# M401M.net
KiCad netlist of a schematic drawn in EAGLE
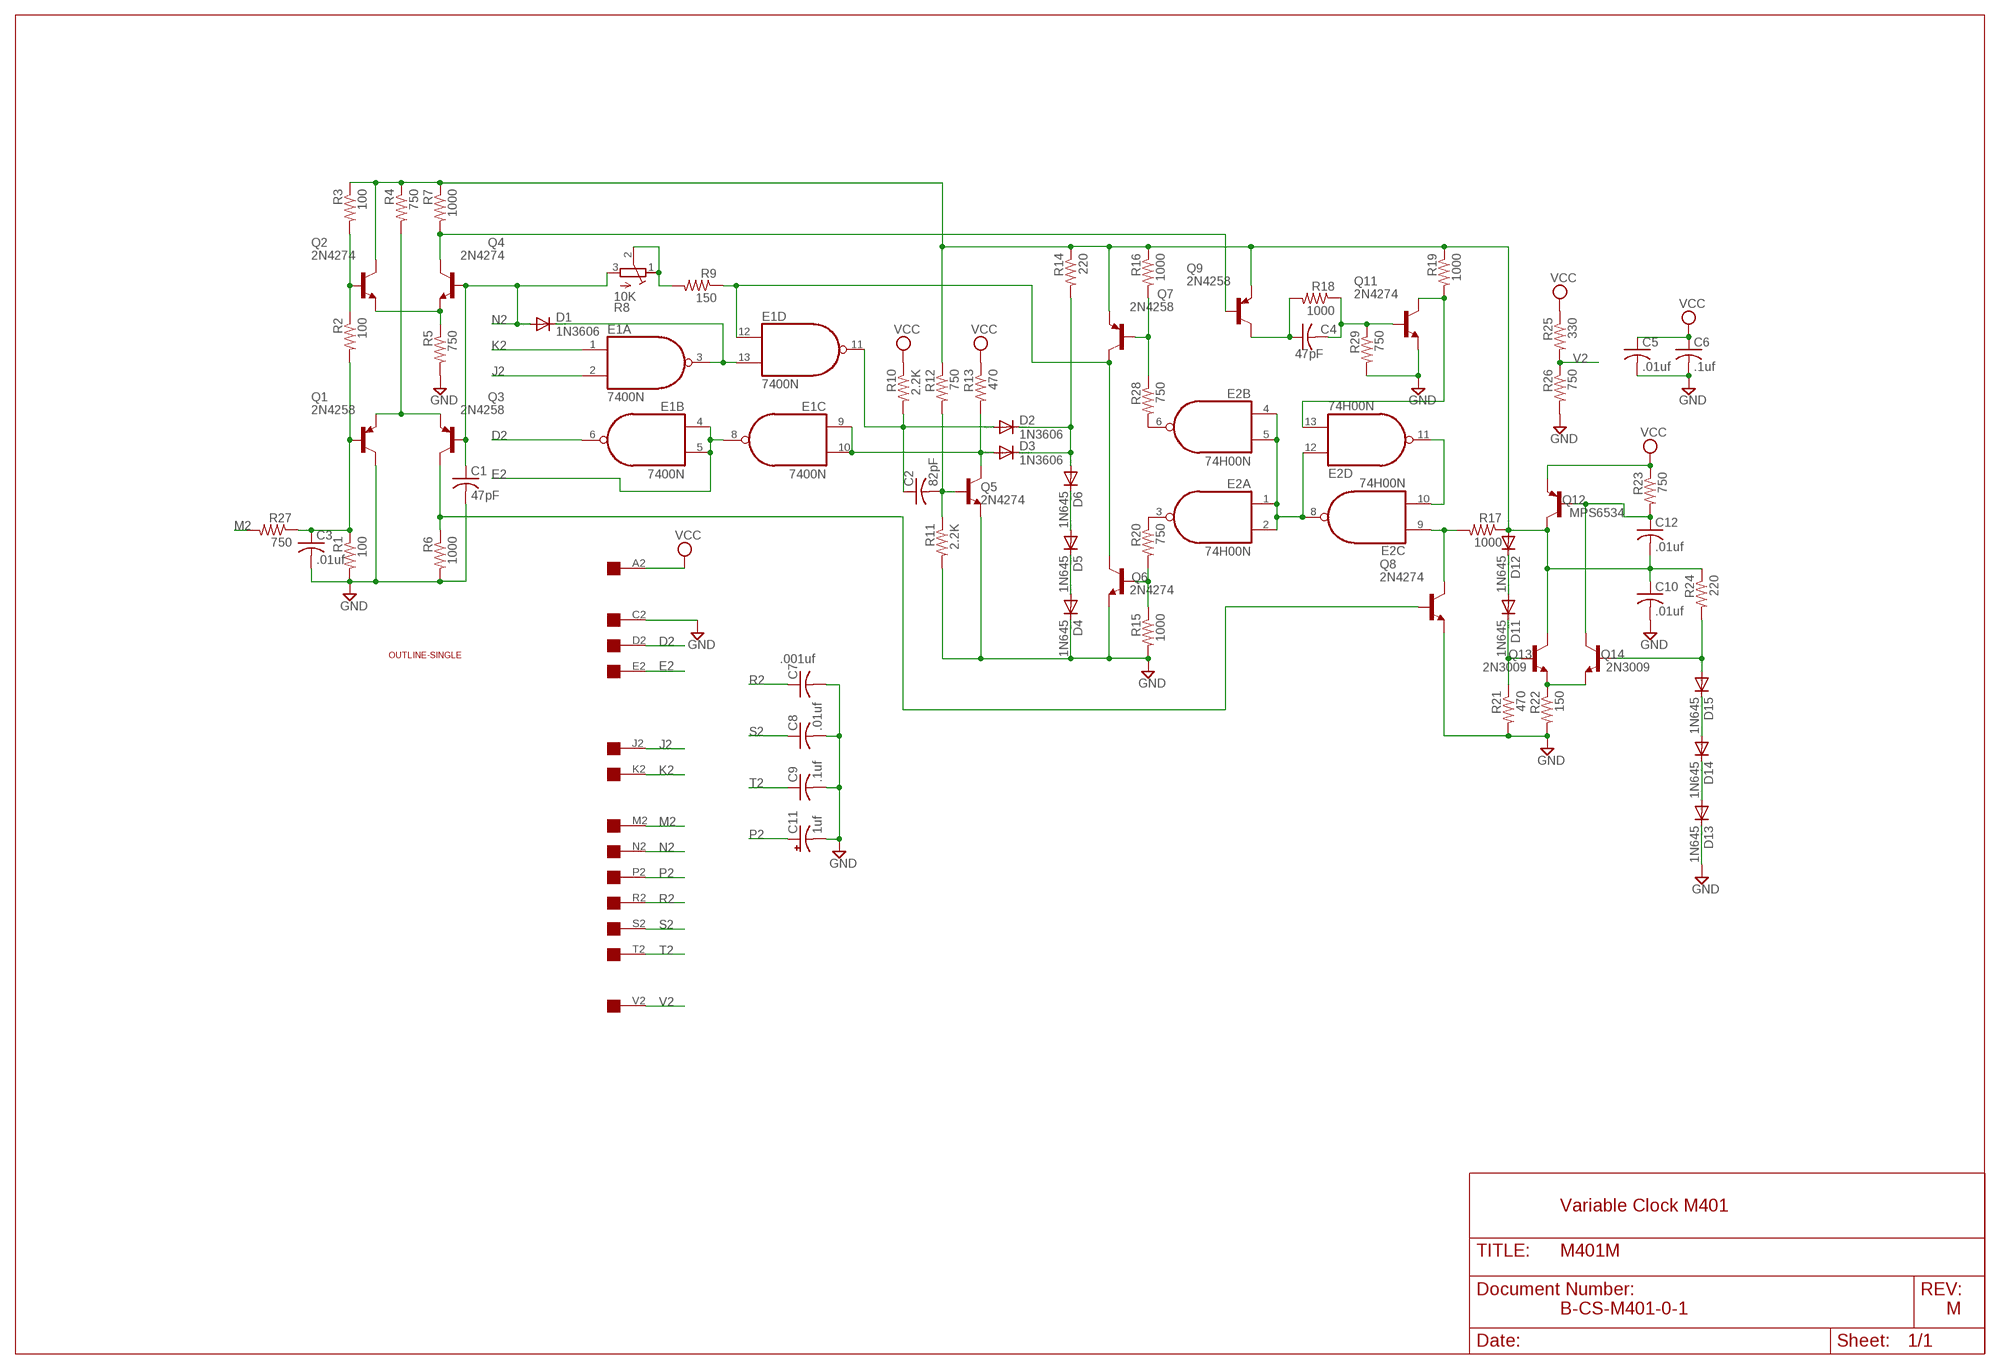
[diagram p0: schematic, sheet 1]

(export (version "E")
  (design (tool "Eeschema 10.0.6"))
  (components
    (comp (ref "C1")
      (value "47pF")
      (footprint "eagle-import:C050-025X075")
      (libsource (lib "eagle-import") (part "C-US050-025X075"))
    )
    (comp (ref "C2")
      (value "82pF")
      (footprint "eagle-import:C050-025X075")
      (libsource (lib "eagle-import") (part "C-US050-025X075"))
    )
    (comp (ref "C3")
      (value ".01uf")
      (footprint "eagle-import:C050-025X075")
      (libsource (lib "eagle-import") (part "C-US050-025X075"))
    )
    (comp (ref "C4")
      (value "47pF")
      (footprint "eagle-import:C050-025X075")
      (libsource (lib "eagle-import") (part "C-US050-025X075"))
    )
    (comp (ref "C5")
      (value ".01uf")
      (footprint "eagle-import:C050-025X075")
      (libsource (lib "eagle-import") (part "C-US050-025X075"))
    )
    (comp (ref "C6")
      (value ".1uf")
      (footprint "eagle-import:C102-043X133")
      (libsource (lib "eagle-import") (part "C-US102-043X133"))
    )
    (comp (ref "C7")
      (value ".001uf")
      (footprint "eagle-import:C050-025X075")
      (libsource (lib "eagle-import") (part "C-US050-025X075"))
    )
    (comp (ref "C8")
      (value ".01uf")
      (footprint "eagle-import:C225-062X268")
      (libsource (lib "eagle-import") (part "C-US225-062X268"))
    )
    (comp (ref "C9")
      (value ".1uf")
      (footprint "eagle-import:C275-093X316")
      (libsource (lib "eagle-import") (part "C-US275-093X316"))
    )
    (comp (ref "C10")
      (value ".01uf")
      (footprint "eagle-import:C050-025X075")
      (libsource (lib "eagle-import") (part "C-US050-025X075"))
    )
    (comp (ref "C11")
      (value "1uf")
      (footprint "eagle-import:E15-5")
      (libsource (lib "eagle-import") (part "CPOL-USE15-5AXIAL"))
    )
    (comp (ref "C12")
      (value ".01uf")
      (footprint "eagle-import:C050-025X075")
      (libsource (lib "eagle-import") (part "C-US050-025X075"))
    )
    (comp (ref "D1")
      (value "1N3606")
      (footprint "eagle-import:DO35-10")
      (libsource (lib "eagle-import") (part "1N4148DO35-10"))
    )
    (comp (ref "D2")
      (value "1N3606")
      (footprint "eagle-import:DO35-10")
      (libsource (lib "eagle-import") (part "1N4148DO35-10"))
    )
    (comp (ref "D3")
      (value "1N3606")
      (footprint "eagle-import:DO35-10")
      (libsource (lib "eagle-import") (part "1N4148DO35-10"))
    )
    (comp (ref "D4")
      (value "1N645")
      (footprint "eagle-import:DO35-10")
      (libsource (lib "eagle-import") (part "1N4148DO35-10"))
    )
    (comp (ref "D5")
      (value "1N645")
      (footprint "eagle-import:DO35-10")
      (libsource (lib "eagle-import") (part "1N4148DO35-10"))
    )
    (comp (ref "D6")
      (value "1N645")
      (footprint "eagle-import:DO35-10")
      (libsource (lib "eagle-import") (part "1N4148DO35-10"))
    )
    (comp (ref "D11")
      (value "1N645")
      (footprint "eagle-import:DO35-10")
      (libsource (lib "eagle-import") (part "1N4148DO35-10"))
    )
    (comp (ref "D12")
      (value "1N645")
      (footprint "eagle-import:DO35-10")
      (libsource (lib "eagle-import") (part "1N4148DO35-10"))
    )
    (comp (ref "D13")
      (value "1N645")
      (footprint "eagle-import:DO35-10")
      (libsource (lib "eagle-import") (part "1N4148DO35-10"))
    )
    (comp (ref "D14")
      (value "1N645")
      (footprint "eagle-import:DO35-10")
      (libsource (lib "eagle-import") (part "1N4148DO35-10"))
    )
    (comp (ref "D15")
      (value "1N645")
      (footprint "eagle-import:DO35-10")
      (libsource (lib "eagle-import") (part "1N4148DO35-10"))
    )
    (comp (ref "E1")
      (value "7400N")
      (footprint "eagle-import:DIL14")
      (libsource (lib "eagle-import") (part "7400N"))
    )
    (comp (ref "E2")
      (value "74H00N")
      (footprint "eagle-import:DIL14")
      (libsource (lib "eagle-import") (part "7400N"))
    )
    (comp (ref "Q1")
      (value "2N4258")
      (footprint "eagle-import:TO39")
      (libsource (lib "eagle-import") (part "-PNP-TO39-EBC2N3637"))
    )
    (comp (ref "Q2")
      (value "2N4274")
      (footprint "eagle-import:TO39")
      (libsource (lib "eagle-import") (part "-NPN-TO39-EBC2N3019"))
    )
    (comp (ref "Q3")
      (value "2N4258")
      (footprint "eagle-import:TO39")
      (libsource (lib "eagle-import") (part "-PNP-TO39-EBC2N3637"))
    )
    (comp (ref "Q4")
      (value "2N4274")
      (footprint "eagle-import:TO39")
      (libsource (lib "eagle-import") (part "-NPN-TO39-EBC2N3019"))
    )
    (comp (ref "Q5")
      (value "2N4274")
      (footprint "eagle-import:TO39")
      (libsource (lib "eagle-import") (part "-NPN-TO39-EBC2N3019"))
    )
    (comp (ref "Q6")
      (value "2N4274")
      (footprint "eagle-import:TO39")
      (libsource (lib "eagle-import") (part "-NPN-TO39-EBC2N3019"))
    )
    (comp (ref "Q7")
      (value "2N4258")
      (footprint "eagle-import:TO39")
      (libsource (lib "eagle-import") (part "-PNP-TO39-EBC2N3637"))
    )
    (comp (ref "Q8")
      (value "2N4274")
      (footprint "eagle-import:TO39")
      (libsource (lib "eagle-import") (part "-NPN-TO39-EBC2N3019"))
    )
    (comp (ref "Q9")
      (value "2N4258")
      (footprint "eagle-import:TO39")
      (libsource (lib "eagle-import") (part "-PNP-TO39-EBC2N3637"))
    )
    (comp (ref "Q11")
      (value "2N4274")
      (footprint "eagle-import:TO39")
      (libsource (lib "eagle-import") (part "-NPN-TO39-EBC2N3019"))
    )
    (comp (ref "Q12")
      (value "MPS6534")
      (footprint "eagle-import:TO39")
      (libsource (lib "eagle-import") (part "-PNP-TO39-EBC2N3637"))
    )
    (comp (ref "Q13")
      (value "2N3009")
      (footprint "eagle-import:TO39")
      (libsource (lib "eagle-import") (part "-NPN-TO39-EBC2N3019"))
    )
    (comp (ref "Q14")
      (value "2N3009")
      (footprint "eagle-import:TO39")
      (libsource (lib "eagle-import") (part "-NPN-TO39-EBC2N3019"))
    )
    (comp (ref "R1")
      (value "100")
      (footprint "eagle-import:0207_10")
      (libsource (lib "eagle-import") (part "R-US_0207/10"))
    )
    (comp (ref "R2")
      (value "100")
      (footprint "eagle-import:0207_10")
      (libsource (lib "eagle-import") (part "R-US_0207/10"))
    )
    (comp (ref "R3")
      (value "100")
      (footprint "eagle-import:0207_10")
      (libsource (lib "eagle-import") (part "R-US_0207/10"))
    )
    (comp (ref "R4")
      (value "750")
      (footprint "eagle-import:0207_10")
      (libsource (lib "eagle-import") (part "R-US_0207/10"))
    )
    (comp (ref "R5")
      (value "750")
      (footprint "eagle-import:0207_10")
      (libsource (lib "eagle-import") (part "R-US_0207/10"))
    )
    (comp (ref "R6")
      (value "1000")
      (footprint "eagle-import:0207_10")
      (libsource (lib "eagle-import") (part "R-US_0207/10"))
    )
    (comp (ref "R7")
      (value "1000")
      (footprint "eagle-import:0207_10")
      (libsource (lib "eagle-import") (part "R-US_0207/10"))
    )
    (comp (ref "R8")
      (value "10K")
      (footprint "eagle-import:3006Y")
      (libsource (lib "eagle-import") (part "275P"))
    )
    (comp (ref "R9")
      (value "150")
      (footprint "eagle-import:0207_10")
      (libsource (lib "eagle-import") (part "R-US_0207/10"))
    )
    (comp (ref "R10")
      (value "2.2K")
      (footprint "eagle-import:0207_10")
      (libsource (lib "eagle-import") (part "R-US_0207/10"))
    )
    (comp (ref "R11")
      (value "2.2K")
      (footprint "eagle-import:0207_10")
      (libsource (lib "eagle-import") (part "R-US_0207/10"))
    )
    (comp (ref "R12")
      (value "750")
      (footprint "eagle-import:0207_10")
      (libsource (lib "eagle-import") (part "R-US_0207/10"))
    )
    (comp (ref "R13")
      (value "470")
      (footprint "eagle-import:0207_10")
      (libsource (lib "eagle-import") (part "R-US_0207/10"))
    )
    (comp (ref "R14")
      (value "220")
      (footprint "eagle-import:0207_10")
      (libsource (lib "eagle-import") (part "R-US_0207/10"))
    )
    (comp (ref "R15")
      (value "1000")
      (footprint "eagle-import:0207_10")
      (libsource (lib "eagle-import") (part "R-US_0207/10"))
    )
    (comp (ref "R16")
      (value "1000")
      (footprint "eagle-import:0207_10")
      (libsource (lib "eagle-import") (part "R-US_0207/10"))
    )
    (comp (ref "R17")
      (value "1000")
      (footprint "eagle-import:0207_10")
      (libsource (lib "eagle-import") (part "R-US_0207/10"))
    )
    (comp (ref "R18")
      (value "1000")
      (footprint "eagle-import:0207_10")
      (libsource (lib "eagle-import") (part "R-US_0207/10"))
    )
    (comp (ref "R19")
      (value "1000")
      (footprint "eagle-import:0207_10")
      (libsource (lib "eagle-import") (part "R-US_0207/10"))
    )
    (comp (ref "R20")
      (value "750")
      (footprint "eagle-import:0207_10")
      (libsource (lib "eagle-import") (part "R-US_0207/10"))
    )
    (comp (ref "R21")
      (value "470")
      (footprint "eagle-import:0207_10")
      (libsource (lib "eagle-import") (part "R-US_0207/10"))
    )
    (comp (ref "R22")
      (value "150")
      (footprint "eagle-import:0207_10")
      (libsource (lib "eagle-import") (part "R-US_0207/10"))
    )
    (comp (ref "R23")
      (value "750")
      (footprint "eagle-import:0207_10")
      (libsource (lib "eagle-import") (part "R-US_0207/10"))
    )
    (comp (ref "R24")
      (value "220")
      (footprint "eagle-import:0207_10")
      (libsource (lib "eagle-import") (part "R-US_0207/10"))
    )
    (comp (ref "R25")
      (value "330")
      (footprint "eagle-import:0207_10")
      (libsource (lib "eagle-import") (part "R-US_0207/10"))
    )
    (comp (ref "R26")
      (value "750")
      (footprint "eagle-import:0207_10")
      (libsource (lib "eagle-import") (part "R-US_0207/10"))
    )
    (comp (ref "R27")
      (value "750")
      (footprint "eagle-import:0207_10")
      (libsource (lib "eagle-import") (part "R-US_0207/10"))
    )
    (comp (ref "R28")
      (value "750")
      (footprint "eagle-import:0207_10")
      (libsource (lib "eagle-import") (part "R-US_0207/10"))
    )
    (comp (ref "R29")
      (value "750")
      (footprint "eagle-import:0207_10")
      (libsource (lib "eagle-import") (part "R-US_0207/10"))
    )
    (comp (ref "U$1")
      (value "OUTLINE-SINGLE")
      (footprint "eagle-import:SINGLE")
      (libsource (lib "eagle-import") (part "OUTLINE-SINGLE"))
    )
    (comp (ref "U$2")
      (value "EDGE-1")
      (footprint "eagle-import:EDGE-CON1")
      (libsource (lib "eagle-import") (part "EDGE-1"))
    )
  )
  (nets
    (net (code "1") (name "/D2") (class "Default")
      (node (ref "E1") (pin "6") (pinfunction "O_6") (pintype "output"))
      (node (ref "U$2") (pin "D2") (pinfunction "1_D2") (pintype "bidirectional"))
    )
    (net (code "2") (name "/E2") (class "Default")
      (node (ref "E1") (pin "4") (pinfunction "I0_4") (pintype "input"))
      (node (ref "E1") (pin "5") (pinfunction "I1_5") (pintype "input"))
      (node (ref "E1") (pin "8") (pinfunction "O_8") (pintype "output"))
      (node (ref "U$2") (pin "E2") (pinfunction "1_E2") (pintype "bidirectional"))
    )
    (net (code "3") (name "/J2") (class "Default")
      (node (ref "E1") (pin "2") (pinfunction "I1_2") (pintype "input"))
      (node (ref "U$2") (pin "J2") (pinfunction "1_J2") (pintype "bidirectional"))
    )
    (net (code "4") (name "/K2") (class "Default")
      (node (ref "E1") (pin "1") (pinfunction "I0_1") (pintype "input"))
      (node (ref "U$2") (pin "K2") (pinfunction "1_K2") (pintype "bidirectional"))
    )
    (net (code "5") (name "/M2") (class "Default")
      (node (ref "R27") (pin "2") (pinfunction "2_2") (pintype "passive"))
      (node (ref "U$2") (pin "M2") (pinfunction "1_M2") (pintype "bidirectional"))
    )
    (net (code "6") (name "/N2") (class "Default")
      (node (ref "C1") (pin "1") (pinfunction "1_1") (pintype "passive"))
      (node (ref "D1") (pin "A") (pinfunction "A_A") (pintype "passive"))
      (node (ref "Q3") (pin "2") (pinfunction "B_2") (pintype "passive"))
      (node (ref "Q4") (pin "2") (pinfunction "B_2") (pintype "passive"))
      (node (ref "R8") (pin "3") (pinfunction "E_3") (pintype "passive"))
      (node (ref "U$2") (pin "N2") (pinfunction "1_N2") (pintype "bidirectional"))
    )
    (net (code "7") (name "/P2") (class "Default")
      (node (ref "C11") (pin "+") (pinfunction "+_+") (pintype "passive"))
      (node (ref "U$2") (pin "P2") (pinfunction "1_P2") (pintype "bidirectional"))
    )
    (net (code "8") (name "/R2") (class "Default")
      (node (ref "C7") (pin "1") (pinfunction "1_1") (pintype "passive"))
      (node (ref "U$2") (pin "R2") (pinfunction "1_R2") (pintype "bidirectional"))
    )
    (net (code "9") (name "/S2") (class "Default")
      (node (ref "C8") (pin "1") (pinfunction "1_1") (pintype "passive"))
      (node (ref "U$2") (pin "S2") (pinfunction "1_S2") (pintype "bidirectional"))
    )
    (net (code "10") (name "/T2") (class "Default")
      (node (ref "C9") (pin "1") (pinfunction "1_1") (pintype "passive"))
      (node (ref "U$2") (pin "T2") (pinfunction "1_T2") (pintype "bidirectional"))
    )
    (net (code "11") (name "/V2") (class "Default")
      (node (ref "R25") (pin "2") (pinfunction "2_2") (pintype "passive"))
      (node (ref "R26") (pin "1") (pinfunction "1_1") (pintype "passive"))
      (node (ref "U$2") (pin "V2") (pinfunction "1_V2") (pintype "bidirectional"))
    )
    (net (code "12") (name "GND") (class "Default")
      (node (ref "C1") (pin "2") (pinfunction "2_2") (pintype "passive"))
      (node (ref "C10") (pin "2") (pinfunction "2_2") (pintype "passive"))
      (node (ref "C11") (pin "-") (pinfunction "-_-") (pintype "passive"))
      (node (ref "C3") (pin "2") (pinfunction "2_2") (pintype "passive"))
      (node (ref "C5") (pin "2") (pinfunction "2_2") (pintype "passive"))
      (node (ref "C6") (pin "2") (pinfunction "2_2") (pintype "passive"))
      (node (ref "C7") (pin "2") (pinfunction "2_2") (pintype "passive"))
      (node (ref "C8") (pin "2") (pinfunction "2_2") (pintype "passive"))
      (node (ref "C9") (pin "2") (pinfunction "2_2") (pintype "passive"))
      (node (ref "D13") (pin "C") (pinfunction "C_C") (pintype "passive"))
      (node (ref "D4") (pin "C") (pinfunction "C_C") (pintype "passive"))
      (node (ref "Q1") (pin "3") (pinfunction "C_3") (pintype "passive"))
      (node (ref "Q11") (pin "1") (pinfunction "E_1") (pintype "passive"))
      (node (ref "Q5") (pin "1") (pinfunction "E_1") (pintype "passive"))
      (node (ref "Q6") (pin "1") (pinfunction "E_1") (pintype "passive"))
      (node (ref "Q8") (pin "1") (pinfunction "E_1") (pintype "passive"))
      (node (ref "R1") (pin "2") (pinfunction "2_2") (pintype "passive"))
      (node (ref "R11") (pin "2") (pinfunction "2_2") (pintype "passive"))
      (node (ref "R15") (pin "2") (pinfunction "2_2") (pintype "passive"))
      (node (ref "R21") (pin "2") (pinfunction "2_2") (pintype "passive"))
      (node (ref "R22") (pin "2") (pinfunction "2_2") (pintype "passive"))
      (node (ref "R26") (pin "2") (pinfunction "2_2") (pintype "passive"))
      (node (ref "R29") (pin "2") (pinfunction "2_2") (pintype "passive"))
      (node (ref "R5") (pin "2") (pinfunction "2_2") (pintype "passive"))
      (node (ref "R6") (pin "2") (pinfunction "2_2") (pintype "passive"))
      (node (ref "U$2") (pin "C2") (pinfunction "1_C2") (pintype "bidirectional"))
    )
    (net (code "13") (name "Net-(D2-PadC)") (class "Default")
      (node (ref "D2") (pin "C") (pinfunction "C_C") (pintype "passive"))
      (node (ref "D3") (pin "C") (pinfunction "C_C") (pintype "passive"))
      (node (ref "D6") (pin "A") (pinfunction "A_A") (pintype "passive"))
      (node (ref "R14") (pin "2") (pinfunction "2_2") (pintype "passive"))
    )
    (net (code "14") (name "Net-(D4-PadA)") (class "Default")
      (node (ref "D4") (pin "A") (pinfunction "A_A") (pintype "passive"))
      (node (ref "D5") (pin "C") (pinfunction "C_C") (pintype "passive"))
    )
    (net (code "15") (name "Net-(D5-PadA)") (class "Default")
      (node (ref "D5") (pin "A") (pinfunction "A_A") (pintype "passive"))
      (node (ref "D6") (pin "C") (pinfunction "C_C") (pintype "passive"))
    )
    (net (code "16") (name "Net-(D11-PadA)") (class "Default")
      (node (ref "D11") (pin "A") (pinfunction "A_A") (pintype "passive"))
      (node (ref "D12") (pin "C") (pinfunction "C_C") (pintype "passive"))
    )
    (net (code "17") (name "Net-(D13-PadA)") (class "Default")
      (node (ref "D13") (pin "A") (pinfunction "A_A") (pintype "passive"))
      (node (ref "D14") (pin "C") (pinfunction "C_C") (pintype "passive"))
    )
    (net (code "18") (name "Net-(D14-PadA)") (class "Default")
      (node (ref "D14") (pin "A") (pinfunction "A_A") (pintype "passive"))
      (node (ref "D15") (pin "C") (pinfunction "C_C") (pintype "passive"))
    )
    (net (code "19") (name "Net-(E1A-O)") (class "Default")
      (node (ref "D1") (pin "C") (pinfunction "C_C") (pintype "passive"))
      (node (ref "E1") (pin "13") (pinfunction "I1_13") (pintype "input"))
      (node (ref "E1") (pin "3") (pinfunction "O_3") (pintype "output"))
    )
    (net (code "20") (name "Net-(E1C-I0)") (class "Default")
      (node (ref "D3") (pin "A") (pinfunction "A_A") (pintype "passive"))
      (node (ref "E1") (pin "10") (pinfunction "I1_10") (pintype "input"))
      (node (ref "E1") (pin "9") (pinfunction "I0_9") (pintype "input"))
      (node (ref "Q5") (pin "3") (pinfunction "C_3") (pintype "passive"))
      (node (ref "R13") (pin "2") (pinfunction "2_2") (pintype "passive"))
    )
    (net (code "21") (name "Net-(E1D-I0)") (class "Default")
      (node (ref "E1") (pin "12") (pinfunction "I0_12") (pintype "input"))
      (node (ref "Q6") (pin "3") (pinfunction "C_3") (pintype "passive"))
      (node (ref "Q7") (pin "3") (pinfunction "C_3") (pintype "passive"))
      (node (ref "R9") (pin "1") (pinfunction "1_1") (pintype "passive"))
    )
    (net (code "22") (name "Net-(E1D-O)") (class "Default")
      (node (ref "C2") (pin "1") (pinfunction "1_1") (pintype "passive"))
      (node (ref "D2") (pin "A") (pinfunction "A_A") (pintype "passive"))
      (node (ref "E1") (pin "11") (pinfunction "O_11") (pintype "output"))
      (node (ref "R10") (pin "2") (pinfunction "2_2") (pintype "passive"))
    )
    (net (code "23") (name "Net-(E2A-I0)") (class "Default")
      (node (ref "E2") (pin "1") (pinfunction "I0_1") (pintype "input"))
      (node (ref "E2") (pin "12") (pinfunction "I0_12") (pintype "input"))
      (node (ref "E2") (pin "2") (pinfunction "I1_2") (pintype "input"))
      (node (ref "E2") (pin "4") (pinfunction "I0_4") (pintype "input"))
      (node (ref "E2") (pin "5") (pinfunction "I1_5") (pintype "input"))
      (node (ref "E2") (pin "8") (pinfunction "O_8") (pintype "output"))
    )
    (net (code "24") (name "Net-(E2A-O)") (class "Default")
      (node (ref "E2") (pin "3") (pinfunction "O_3") (pintype "output"))
      (node (ref "R20") (pin "1") (pinfunction "1_1") (pintype "passive"))
    )
    (net (code "25") (name "Net-(E2B-O)") (class "Default")
      (node (ref "E2") (pin "6") (pinfunction "O_6") (pintype "output"))
      (node (ref "R28") (pin "2") (pinfunction "2_2") (pintype "passive"))
    )
    (net (code "26") (name "Net-(E2C-I0)") (class "Default")
      (node (ref "E2") (pin "9") (pinfunction "I0_9") (pintype "input"))
      (node (ref "Q8") (pin "3") (pinfunction "C_3") (pintype "passive"))
      (node (ref "R17") (pin "2") (pinfunction "2_2") (pintype "passive"))
    )
    (net (code "27") (name "Net-(E2C-I1)") (class "Default")
      (node (ref "E2") (pin "10") (pinfunction "I1_10") (pintype "input"))
      (node (ref "E2") (pin "11") (pinfunction "O_11") (pintype "output"))
    )
    (net (code "28") (name "Net-(E2D-I1)") (class "Default")
      (node (ref "E2") (pin "13") (pinfunction "I1_13") (pintype "input"))
      (node (ref "Q11") (pin "3") (pinfunction "C_3") (pintype "passive"))
      (node (ref "R19") (pin "2") (pinfunction "2_2") (pintype "passive"))
    )
    (net (code "29") (name "Net-(Q1-B)") (class "Default")
      (node (ref "C3") (pin "1") (pinfunction "1_1") (pintype "passive"))
      (node (ref "Q1") (pin "2") (pinfunction "B_2") (pintype "passive"))
      (node (ref "R1") (pin "1") (pinfunction "1_1") (pintype "passive"))
      (node (ref "R2") (pin "2") (pinfunction "2_2") (pintype "passive"))
      (node (ref "R27") (pin "1") (pinfunction "1_1") (pintype "passive"))
    )
    (net (code "30") (name "Net-(Q1-E)") (class "Default")
      (node (ref "Q1") (pin "1") (pinfunction "E_1") (pintype "passive"))
      (node (ref "Q3") (pin "1") (pinfunction "E_1") (pintype "passive"))
      (node (ref "R4") (pin "2") (pinfunction "2_2") (pintype "passive"))
    )
    (net (code "31") (name "Net-(Q2-B)") (class "Default")
      (node (ref "Q2") (pin "2") (pinfunction "B_2") (pintype "passive"))
      (node (ref "R2") (pin "1") (pinfunction "1_1") (pintype "passive"))
      (node (ref "R3") (pin "2") (pinfunction "2_2") (pintype "passive"))
    )
    (net (code "32") (name "Net-(Q2-E)") (class "Default")
      (node (ref "Q2") (pin "1") (pinfunction "E_1") (pintype "passive"))
      (node (ref "Q4") (pin "1") (pinfunction "E_1") (pintype "passive"))
      (node (ref "R5") (pin "1") (pinfunction "1_1") (pintype "passive"))
    )
    (net (code "33") (name "Net-(Q3-C)") (class "Default")
      (node (ref "Q3") (pin "3") (pinfunction "C_3") (pintype "passive"))
      (node (ref "Q8") (pin "2") (pinfunction "B_2") (pintype "passive"))
      (node (ref "R6") (pin "1") (pinfunction "1_1") (pintype "passive"))
    )
    (net (code "34") (name "Net-(Q4-C)") (class "Default")
      (node (ref "Q4") (pin "3") (pinfunction "C_3") (pintype "passive"))
      (node (ref "Q9") (pin "2") (pinfunction "B_2") (pintype "passive"))
      (node (ref "R7") (pin "2") (pinfunction "2_2") (pintype "passive"))
    )
    (net (code "35") (name "Net-(Q5-B)") (class "Default")
      (node (ref "C2") (pin "2") (pinfunction "2_2") (pintype "passive"))
      (node (ref "Q5") (pin "2") (pinfunction "B_2") (pintype "passive"))
      (node (ref "R11") (pin "1") (pinfunction "1_1") (pintype "passive"))
      (node (ref "R12") (pin "2") (pinfunction "2_2") (pintype "passive"))
    )
    (net (code "36") (name "Net-(Q6-B)") (class "Default")
      (node (ref "Q6") (pin "2") (pinfunction "B_2") (pintype "passive"))
      (node (ref "R15") (pin "1") (pinfunction "1_1") (pintype "passive"))
      (node (ref "R20") (pin "2") (pinfunction "2_2") (pintype "passive"))
    )
    (net (code "37") (name "Net-(Q7-B)") (class "Default")
      (node (ref "Q7") (pin "2") (pinfunction "B_2") (pintype "passive"))
      (node (ref "R16") (pin "2") (pinfunction "2_2") (pintype "passive"))
      (node (ref "R28") (pin "1") (pinfunction "1_1") (pintype "passive"))
    )
    (net (code "38") (name "Net-(Q9-C)") (class "Default")
      (node (ref "C4") (pin "1") (pinfunction "1_1") (pintype "passive"))
      (node (ref "Q9") (pin "3") (pinfunction "C_3") (pintype "passive"))
      (node (ref "R18") (pin "2") (pinfunction "2_2") (pintype "passive"))
    )
    (net (code "39") (name "Net-(Q11-B)") (class "Default")
      (node (ref "C4") (pin "2") (pinfunction "2_2") (pintype "passive"))
      (node (ref "Q11") (pin "2") (pinfunction "B_2") (pintype "passive"))
      (node (ref "R18") (pin "1") (pinfunction "1_1") (pintype "passive"))
      (node (ref "R29") (pin "1") (pinfunction "1_1") (pintype "passive"))
    )
    (net (code "40") (name "Net-(Q12-B)") (class "Default")
      (node (ref "C12") (pin "1") (pinfunction "1_1") (pintype "passive"))
      (node (ref "Q12") (pin "2") (pinfunction "B_2") (pintype "passive"))
      (node (ref "Q14") (pin "3") (pinfunction "C_3") (pintype "passive"))
      (node (ref "R23") (pin "2") (pinfunction "2_2") (pintype "passive"))
    )
    (net (code "41") (name "Net-(Q12-C)") (class "Default")
      (node (ref "C10") (pin "1") (pinfunction "1_1") (pintype "passive"))
      (node (ref "C12") (pin "2") (pinfunction "2_2") (pintype "passive"))
      (node (ref "D12") (pin "A") (pinfunction "A_A") (pintype "passive"))
      (node (ref "Q12") (pin "3") (pinfunction "C_3") (pintype "passive"))
      (node (ref "Q13") (pin "3") (pinfunction "C_3") (pintype "passive"))
      (node (ref "Q2") (pin "3") (pinfunction "C_3") (pintype "passive"))
      (node (ref "Q7") (pin "1") (pinfunction "E_1") (pintype "passive"))
      (node (ref "Q9") (pin "1") (pinfunction "E_1") (pintype "passive"))
      (node (ref "R12") (pin "1") (pinfunction "1_1") (pintype "passive"))
      (node (ref "R14") (pin "1") (pinfunction "1_1") (pintype "passive"))
      (node (ref "R16") (pin "1") (pinfunction "1_1") (pintype "passive"))
      (node (ref "R17") (pin "1") (pinfunction "1_1") (pintype "passive"))
      (node (ref "R19") (pin "1") (pinfunction "1_1") (pintype "passive"))
      (node (ref "R24") (pin "1") (pinfunction "1_1") (pintype "passive"))
      (node (ref "R3") (pin "1") (pinfunction "1_1") (pintype "passive"))
      (node (ref "R4") (pin "1") (pinfunction "1_1") (pintype "passive"))
      (node (ref "R7") (pin "1") (pinfunction "1_1") (pintype "passive"))
    )
    (net (code "42") (name "Net-(Q13-B)") (class "Default")
      (node (ref "D11") (pin "C") (pinfunction "C_C") (pintype "passive"))
      (node (ref "Q13") (pin "2") (pinfunction "B_2") (pintype "passive"))
      (node (ref "R21") (pin "1") (pinfunction "1_1") (pintype "passive"))
    )
    (net (code "43") (name "Net-(Q13-E)") (class "Default")
      (node (ref "Q13") (pin "1") (pinfunction "E_1") (pintype "passive"))
      (node (ref "Q14") (pin "1") (pinfunction "E_1") (pintype "passive"))
      (node (ref "R22") (pin "1") (pinfunction "1_1") (pintype "passive"))
    )
    (net (code "44") (name "Net-(Q14-B)") (class "Default")
      (node (ref "D15") (pin "A") (pinfunction "A_A") (pintype "passive"))
      (node (ref "Q14") (pin "2") (pinfunction "B_2") (pintype "passive"))
      (node (ref "R24") (pin "2") (pinfunction "2_2") (pintype "passive"))
    )
    (net (code "45") (name "Net-(R8-A)") (class "Default")
      (node (ref "R8") (pin "1") (pinfunction "A_1") (pintype "passive"))
      (node (ref "R8") (pin "2") (pinfunction "S_2") (pintype "passive"))
      (node (ref "R9") (pin "2") (pinfunction "2_2") (pintype "passive"))
    )
    (net (code "46") (name "VCC") (class "Default")
      (node (ref "C5") (pin "1") (pinfunction "1_1") (pintype "passive"))
      (node (ref "C6") (pin "1") (pinfunction "1_1") (pintype "passive"))
      (node (ref "Q12") (pin "1") (pinfunction "E_1") (pintype "passive"))
      (node (ref "R10") (pin "1") (pinfunction "1_1") (pintype "passive"))
      (node (ref "R13") (pin "1") (pinfunction "1_1") (pintype "passive"))
      (node (ref "R23") (pin "1") (pinfunction "1_1") (pintype "passive"))
      (node (ref "R25") (pin "1") (pinfunction "1_1") (pintype "passive"))
      (node (ref "U$2") (pin "A2") (pinfunction "1_A2") (pintype "bidirectional"))
    )
  )
)
